# board.net
KiCad netlist of a schematic drawn in EAGLE
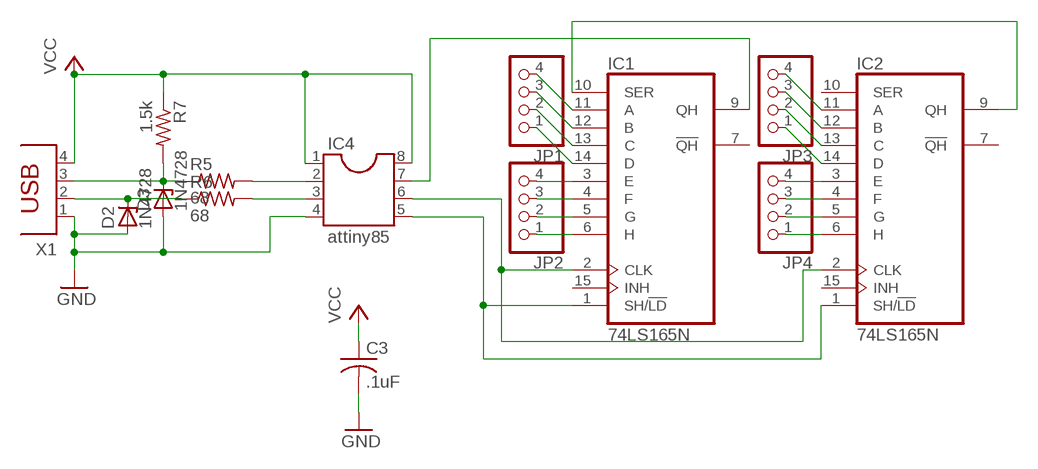
[diagram p0: schematic, sheet 1]

(export (version "E")
  (design (tool "Eeschema 10.0.6"))
  (components
    (comp (ref "C3")
      (value ".1uF")
      (footprint "eagle-import:C025-024X044")
      (libsource (lib "eagle-import") (part "C-US025-024X044"))
    )
    (comp (ref "D2")
      (value "1N4728")
      (footprint "eagle-import:DO41Z10")
      (libsource (lib "eagle-import") (part "1N4728"))
    )
    (comp (ref "D3")
      (value "1N4728")
      (footprint "eagle-import:DO41Z10")
      (libsource (lib "eagle-import") (part "1N4728"))
    )
    (comp (ref "IC1")
      (value "74LS165N")
      (footprint "eagle-import:DIL16")
      (libsource (lib "eagle-import") (part "74165NLS"))
    )
    (comp (ref "IC2")
      (value "74LS165N")
      (footprint "eagle-import:DIL16")
      (libsource (lib "eagle-import") (part "74165NLS"))
    )
    (comp (ref "IC4")
      (value "attiny85")
      (footprint "eagle-import:SOCKET-08")
      (libsource (lib "eagle-import") (part "DIL8S"))
    )
    (comp (ref "JP1")
      (value "PINHD-1X4")
      (footprint "eagle-import:1X04")
      (libsource (lib "eagle-import") (part "PINHD-1X4"))
    )
    (comp (ref "JP2")
      (value "PINHD-1X4")
      (footprint "eagle-import:1X04")
      (libsource (lib "eagle-import") (part "PINHD-1X4"))
    )
    (comp (ref "JP3")
      (value "PINHD-1X4")
      (footprint "eagle-import:1X04")
      (libsource (lib "eagle-import") (part "PINHD-1X4"))
    )
    (comp (ref "JP4")
      (value "PINHD-1X4")
      (footprint "eagle-import:1X04")
      (libsource (lib "eagle-import") (part "PINHD-1X4"))
    )
    (comp (ref "R5")
      (value "68")
      (footprint "eagle-import:0204_7")
      (libsource (lib "eagle-import") (part "R-US_0204/7"))
    )
    (comp (ref "R6")
      (value "68")
      (footprint "eagle-import:0204_7")
      (libsource (lib "eagle-import") (part "R-US_0204/7"))
    )
    (comp (ref "R7")
      (value "1.5k")
      (footprint "eagle-import:0204_7")
      (libsource (lib "eagle-import") (part "R-US_0204/7"))
    )
    (comp (ref "X1")
      (value "PN87520")
      (footprint "eagle-import:PN87520")
      (libsource (lib "eagle-import") (part "PN87520"))
    )
  )
  (nets
    (net (code "1") (name "GND") (class "Default")
      (node (ref "C3") (pin "2") (pinfunction "2_2") (pintype "passive"))
      (node (ref "D2") (pin "A") (pinfunction "A_A") (pintype "passive"))
      (node (ref "D3") (pin "A") (pinfunction "A_A") (pintype "passive"))
      (node (ref "IC4") (pin "4") (pinfunction "4_4") (pintype "passive"))
      (node (ref "X1") (pin "1") (pinfunction "1_1") (pintype "passive"))
    )
    (net (code "2") (name "Net-(D2-PadC)") (class "Default")
      (node (ref "D2") (pin "C") (pinfunction "C_C") (pintype "passive"))
      (node (ref "R6") (pin "1") (pinfunction "1_1") (pintype "passive"))
      (node (ref "X1") (pin "2") (pinfunction "2_2") (pintype "passive"))
    )
    (net (code "3") (name "Net-(D3-PadC)") (class "Default")
      (node (ref "D3") (pin "C") (pinfunction "C_C") (pintype "passive"))
      (node (ref "R5") (pin "1") (pinfunction "1_1") (pintype "passive"))
      (node (ref "R7") (pin "2") (pinfunction "2_2") (pintype "passive"))
      (node (ref "X1") (pin "3") (pinfunction "3_3") (pintype "passive"))
    )
    (net (code "4") (name "Net-(IC1A-A)") (class "Default")
      (node (ref "IC1") (pin "11") (pinfunction "A_11") (pintype "input"))
      (node (ref "JP1") (pin "4") (pinfunction "4_4") (pintype "passive"))
    )
    (net (code "5") (name "Net-(IC1A-B)") (class "Default")
      (node (ref "IC1") (pin "12") (pinfunction "B_12") (pintype "input"))
      (node (ref "JP1") (pin "3") (pinfunction "3_3") (pintype "passive"))
    )
    (net (code "6") (name "Net-(IC1A-C)") (class "Default")
      (node (ref "IC1") (pin "13") (pinfunction "C_13") (pintype "input"))
      (node (ref "JP1") (pin "2") (pinfunction "2_2") (pintype "passive"))
    )
    (net (code "7") (name "Net-(IC1A-CLK)") (class "Default")
      (node (ref "IC1") (pin "2") (pinfunction "CLK_2") (pintype "input"))
      (node (ref "IC2") (pin "2") (pinfunction "CLK_2") (pintype "input"))
      (node (ref "IC4") (pin "6") (pinfunction "6_6") (pintype "passive"))
    )
    (net (code "8") (name "Net-(IC1A-D)") (class "Default")
      (node (ref "IC1") (pin "14") (pinfunction "D_14") (pintype "input"))
      (node (ref "JP1") (pin "1") (pinfunction "1_1") (pintype "passive"))
    )
    (net (code "9") (name "Net-(IC1A-E)") (class "Default")
      (node (ref "IC1") (pin "3") (pinfunction "E_3") (pintype "input"))
      (node (ref "JP2") (pin "4") (pinfunction "4_4") (pintype "passive"))
    )
    (net (code "10") (name "Net-(IC1A-F)") (class "Default")
      (node (ref "IC1") (pin "4") (pinfunction "F_4") (pintype "input"))
      (node (ref "JP2") (pin "3") (pinfunction "3_3") (pintype "passive"))
    )
    (net (code "11") (name "Net-(IC1A-G)") (class "Default")
      (node (ref "IC1") (pin "5") (pinfunction "G_5") (pintype "input"))
      (node (ref "JP2") (pin "2") (pinfunction "2_2") (pintype "passive"))
    )
    (net (code "12") (name "Net-(IC1A-H)") (class "Default")
      (node (ref "IC1") (pin "6") (pinfunction "H_6") (pintype "input"))
      (node (ref "JP2") (pin "1") (pinfunction "1_1") (pintype "passive"))
    )
    (net (code "13") (name "Net-(IC1A-QH)") (class "Default")
      (node (ref "IC1") (pin "9") (pinfunction "QH_9") (pintype "output"))
      (node (ref "IC4") (pin "7") (pinfunction "7_7") (pintype "passive"))
    )
    (net (code "14") (name "Net-(IC1A-SER)") (class "Default")
      (node (ref "IC1") (pin "10") (pinfunction "SER_10") (pintype "input"))
      (node (ref "IC2") (pin "9") (pinfunction "QH_9") (pintype "output"))
    )
    (net (code "15") (name "Net-(IC1A-SH{slash}~{LD})") (class "Default")
      (node (ref "IC1") (pin "1") (pinfunction "SH/~{LD}_1") (pintype "input"))
      (node (ref "IC2") (pin "1") (pinfunction "SH/~{LD}_1") (pintype "input"))
      (node (ref "IC4") (pin "5") (pinfunction "5_5") (pintype "passive"))
    )
    (net (code "16") (name "Net-(IC2A-A)") (class "Default")
      (node (ref "IC2") (pin "11") (pinfunction "A_11") (pintype "input"))
      (node (ref "JP3") (pin "4") (pinfunction "4_4") (pintype "passive"))
    )
    (net (code "17") (name "Net-(IC2A-B)") (class "Default")
      (node (ref "IC2") (pin "12") (pinfunction "B_12") (pintype "input"))
      (node (ref "JP3") (pin "3") (pinfunction "3_3") (pintype "passive"))
    )
    (net (code "18") (name "Net-(IC2A-C)") (class "Default")
      (node (ref "IC2") (pin "13") (pinfunction "C_13") (pintype "input"))
      (node (ref "JP3") (pin "2") (pinfunction "2_2") (pintype "passive"))
    )
    (net (code "19") (name "Net-(IC2A-D)") (class "Default")
      (node (ref "IC2") (pin "14") (pinfunction "D_14") (pintype "input"))
      (node (ref "JP3") (pin "1") (pinfunction "1_1") (pintype "passive"))
    )
    (net (code "20") (name "Net-(IC2A-E)") (class "Default")
      (node (ref "IC2") (pin "3") (pinfunction "E_3") (pintype "input"))
      (node (ref "JP4") (pin "4") (pinfunction "4_4") (pintype "passive"))
    )
    (net (code "21") (name "Net-(IC2A-F)") (class "Default")
      (node (ref "IC2") (pin "4") (pinfunction "F_4") (pintype "input"))
      (node (ref "JP4") (pin "3") (pinfunction "3_3") (pintype "passive"))
    )
    (net (code "22") (name "Net-(IC2A-G)") (class "Default")
      (node (ref "IC2") (pin "5") (pinfunction "G_5") (pintype "input"))
      (node (ref "JP4") (pin "2") (pinfunction "2_2") (pintype "passive"))
    )
    (net (code "23") (name "Net-(IC2A-H)") (class "Default")
      (node (ref "IC2") (pin "6") (pinfunction "H_6") (pintype "input"))
      (node (ref "JP4") (pin "1") (pinfunction "1_1") (pintype "passive"))
    )
    (net (code "24") (name "Net-(IC4-Pad2)") (class "Default")
      (node (ref "IC4") (pin "2") (pinfunction "2_2") (pintype "passive"))
      (node (ref "R5") (pin "2") (pinfunction "2_2") (pintype "passive"))
    )
    (net (code "25") (name "Net-(IC4-Pad3)") (class "Default")
      (node (ref "IC4") (pin "3") (pinfunction "3_3") (pintype "passive"))
      (node (ref "R6") (pin "2") (pinfunction "2_2") (pintype "passive"))
    )
    (net (code "26") (name "VCC") (class "Default")
      (node (ref "C3") (pin "1") (pinfunction "1_1") (pintype "passive"))
      (node (ref "IC4") (pin "1") (pinfunction "1_1") (pintype "passive"))
      (node (ref "IC4") (pin "8") (pinfunction "8_8") (pintype "passive"))
      (node (ref "R7") (pin "1") (pinfunction "1_1") (pintype "passive"))
      (node (ref "X1") (pin "4") (pinfunction "4_4") (pintype "passive"))
    )
    (net (code "27") (name "unconnected-(IC1A-INH-Pad15)") (class "Default")
      (node (ref "IC1") (pin "15") (pinfunction "INH_15") (pintype "input"))
    )
    (net (code "28") (name "unconnected-(IC1A-~{QH}-Pad7)") (class "Default")
      (node (ref "IC1") (pin "7") (pinfunction "~{QH}_7") (pintype "output"))
    )
    (net (code "29") (name "unconnected-(IC2A-INH-Pad15)") (class "Default")
      (node (ref "IC2") (pin "15") (pinfunction "INH_15") (pintype "input"))
    )
    (net (code "30") (name "unconnected-(IC2A-SER-Pad10)") (class "Default")
      (node (ref "IC2") (pin "10") (pinfunction "SER_10") (pintype "input"))
    )
    (net (code "31") (name "unconnected-(IC2A-~{QH}-Pad7)") (class "Default")
      (node (ref "IC2") (pin "7") (pinfunction "~{QH}_7") (pintype "output"))
    )
  )
)
